# ATmegaProgramming.net
KiCad netlist of a schematic drawn in EAGLE
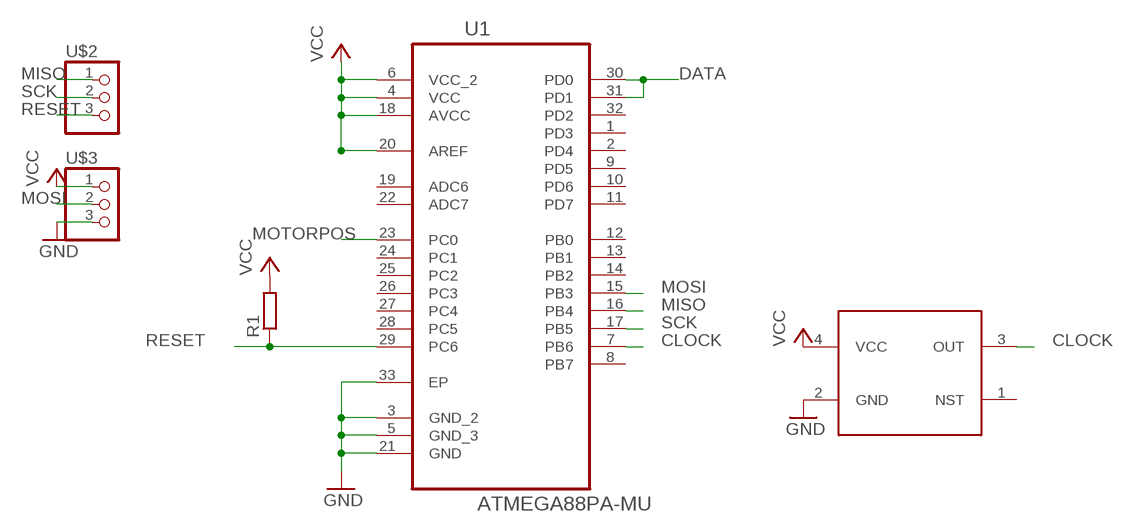
[diagram p0: schematic, sheet 1]

(export (version "E")
  (design (tool "Eeschema 10.0.6"))
  (components
    (comp (ref "R1")
      (value "R-EU_0414/15")
      (footprint "eagle-import:0414_15")
      (libsource (lib "eagle-import") (part "R-EU_0414/15"))
    )
    (comp (ref "U$1")
      (value "SG-310")
      (footprint "eagle-import:SG-310")
      (libsource (lib "eagle-import") (part "SG-310"))
    )
    (comp (ref "U$2")
      (value "CONNEC_1X03")
      (footprint "eagle-import:CONNEC_1X03")
      (libsource (lib "eagle-import") (part "CONNEC_1X03"))
    )
    (comp (ref "U$3")
      (value "CONNEC_1X03")
      (footprint "eagle-import:CONNEC_1X03")
      (libsource (lib "eagle-import") (part "CONNEC_1X03"))
    )
    (comp (ref "U1")
      (value "ATMEGA88PA-MU")
      (footprint "eagle-import:QFN50P500X500X100-33N")
      (libsource (lib "eagle-import") (part "ATMEGA88PA-MU"))
    )
  )
  (nets
    (net (code "1") (name "/CLOCK") (class "Default")
      (node (ref "U$1") (pin "3") (pinfunction "OUT_3") (pintype "bidirectional"))
      (node (ref "U1") (pin "7") (pinfunction "PB6_7") (pintype "bidirectional"))
    )
    (net (code "2") (name "/DATA") (class "Default")
      (node (ref "U1") (pin "30") (pinfunction "PD0_30") (pintype "bidirectional"))
      (node (ref "U1") (pin "31") (pinfunction "PD1_31") (pintype "bidirectional"))
    )
    (net (code "3") (name "/MISO") (class "Default")
      (node (ref "U$2") (pin "1") (pinfunction "1_1") (pintype "passive"))
      (node (ref "U1") (pin "16") (pinfunction "PB4_16") (pintype "bidirectional"))
    )
    (net (code "4") (name "/MOSI") (class "Default")
      (node (ref "U$3") (pin "2") (pinfunction "2_2") (pintype "passive"))
      (node (ref "U1") (pin "15") (pinfunction "PB3_15") (pintype "bidirectional"))
    )
    (net (code "5") (name "/MOTORPOS") (class "Default")
      (node (ref "U1") (pin "23") (pinfunction "PC0_23") (pintype "bidirectional"))
    )
    (net (code "6") (name "/RESET") (class "Default")
      (node (ref "R1") (pin "1") (pinfunction "1_1") (pintype "passive"))
      (node (ref "U$2") (pin "3") (pinfunction "3_3") (pintype "passive"))
      (node (ref "U1") (pin "29") (pinfunction "PC6_29") (pintype "bidirectional"))
    )
    (net (code "7") (name "/SCK") (class "Default")
      (node (ref "U$2") (pin "2") (pinfunction "2_2") (pintype "passive"))
      (node (ref "U1") (pin "17") (pinfunction "PB5_17") (pintype "bidirectional"))
    )
    (net (code "8") (name "GND") (class "Default")
      (node (ref "U$1") (pin "2") (pinfunction "GND_2") (pintype "bidirectional"))
      (node (ref "U$3") (pin "3") (pinfunction "3_3") (pintype "passive"))
      (node (ref "U1") (pin "21") (pinfunction "GND_21") (pintype "passive"))
      (node (ref "U1") (pin "3") (pinfunction "GND_2_3") (pintype "passive"))
      (node (ref "U1") (pin "33") (pinfunction "EP_33") (pintype "passive"))
      (node (ref "U1") (pin "5") (pinfunction "GND_3_5") (pintype "passive"))
    )
    (net (code "9") (name "VCC") (class "Default")
      (node (ref "R1") (pin "2") (pinfunction "2_2") (pintype "passive"))
      (node (ref "U$1") (pin "4") (pinfunction "VCC_4") (pintype "bidirectional"))
      (node (ref "U$3") (pin "1") (pinfunction "1_1") (pintype "passive"))
      (node (ref "U1") (pin "18") (pinfunction "AVCC_18") (pintype "power_in"))
      (node (ref "U1") (pin "20") (pinfunction "AREF_20") (pintype "input"))
      (node (ref "U1") (pin "4") (pinfunction "VCC_4") (pintype "power_in"))
      (node (ref "U1") (pin "6") (pinfunction "VCC_2_6") (pintype "power_in"))
    )
    (net (code "10") (name "unconnected-(U$1-NST-Pad1)") (class "Default")
      (node (ref "U$1") (pin "1") (pinfunction "NST_1") (pintype "bidirectional"))
    )
    (net (code "11") (name "unconnected-(U1-ADC6-Pad19)") (class "Default")
      (node (ref "U1") (pin "19") (pinfunction "ADC6_19") (pintype "input"))
    )
    (net (code "12") (name "unconnected-(U1-ADC7-Pad22)") (class "Default")
      (node (ref "U1") (pin "22") (pinfunction "ADC7_22") (pintype "input"))
    )
    (net (code "13") (name "unconnected-(U1-PB0-Pad12)") (class "Default")
      (node (ref "U1") (pin "12") (pinfunction "PB0_12") (pintype "bidirectional"))
    )
    (net (code "14") (name "unconnected-(U1-PB1-Pad13)") (class "Default")
      (node (ref "U1") (pin "13") (pinfunction "PB1_13") (pintype "bidirectional"))
    )
    (net (code "15") (name "unconnected-(U1-PB2-Pad14)") (class "Default")
      (node (ref "U1") (pin "14") (pinfunction "PB2_14") (pintype "bidirectional"))
    )
    (net (code "16") (name "unconnected-(U1-PB7-Pad8)") (class "Default")
      (node (ref "U1") (pin "8") (pinfunction "PB7_8") (pintype "bidirectional"))
    )
    (net (code "17") (name "unconnected-(U1-PC1-Pad24)") (class "Default")
      (node (ref "U1") (pin "24") (pinfunction "PC1_24") (pintype "bidirectional"))
    )
    (net (code "18") (name "unconnected-(U1-PC2-Pad25)") (class "Default")
      (node (ref "U1") (pin "25") (pinfunction "PC2_25") (pintype "bidirectional"))
    )
    (net (code "19") (name "unconnected-(U1-PC3-Pad26)") (class "Default")
      (node (ref "U1") (pin "26") (pinfunction "PC3_26") (pintype "bidirectional"))
    )
    (net (code "20") (name "unconnected-(U1-PC4-Pad27)") (class "Default")
      (node (ref "U1") (pin "27") (pinfunction "PC4_27") (pintype "bidirectional"))
    )
    (net (code "21") (name "unconnected-(U1-PC5-Pad28)") (class "Default")
      (node (ref "U1") (pin "28") (pinfunction "PC5_28") (pintype "bidirectional"))
    )
    (net (code "22") (name "unconnected-(U1-PD2-Pad32)") (class "Default")
      (node (ref "U1") (pin "32") (pinfunction "PD2_32") (pintype "bidirectional"))
    )
    (net (code "23") (name "unconnected-(U1-PD3-Pad1)") (class "Default")
      (node (ref "U1") (pin "1") (pinfunction "PD3_1") (pintype "bidirectional"))
    )
    (net (code "24") (name "unconnected-(U1-PD4-Pad2)") (class "Default")
      (node (ref "U1") (pin "2") (pinfunction "PD4_2") (pintype "bidirectional"))
    )
    (net (code "25") (name "unconnected-(U1-PD5-Pad9)") (class "Default")
      (node (ref "U1") (pin "9") (pinfunction "PD5_9") (pintype "bidirectional"))
    )
    (net (code "26") (name "unconnected-(U1-PD6-Pad10)") (class "Default")
      (node (ref "U1") (pin "10") (pinfunction "PD6_10") (pintype "bidirectional"))
    )
    (net (code "27") (name "unconnected-(U1-PD7-Pad11)") (class "Default")
      (node (ref "U1") (pin "11") (pinfunction "PD7_11") (pintype "bidirectional"))
    )
  )
)
